# PowersupplyCommutation.net
KiCad netlist of a schematic drawn in EAGLE
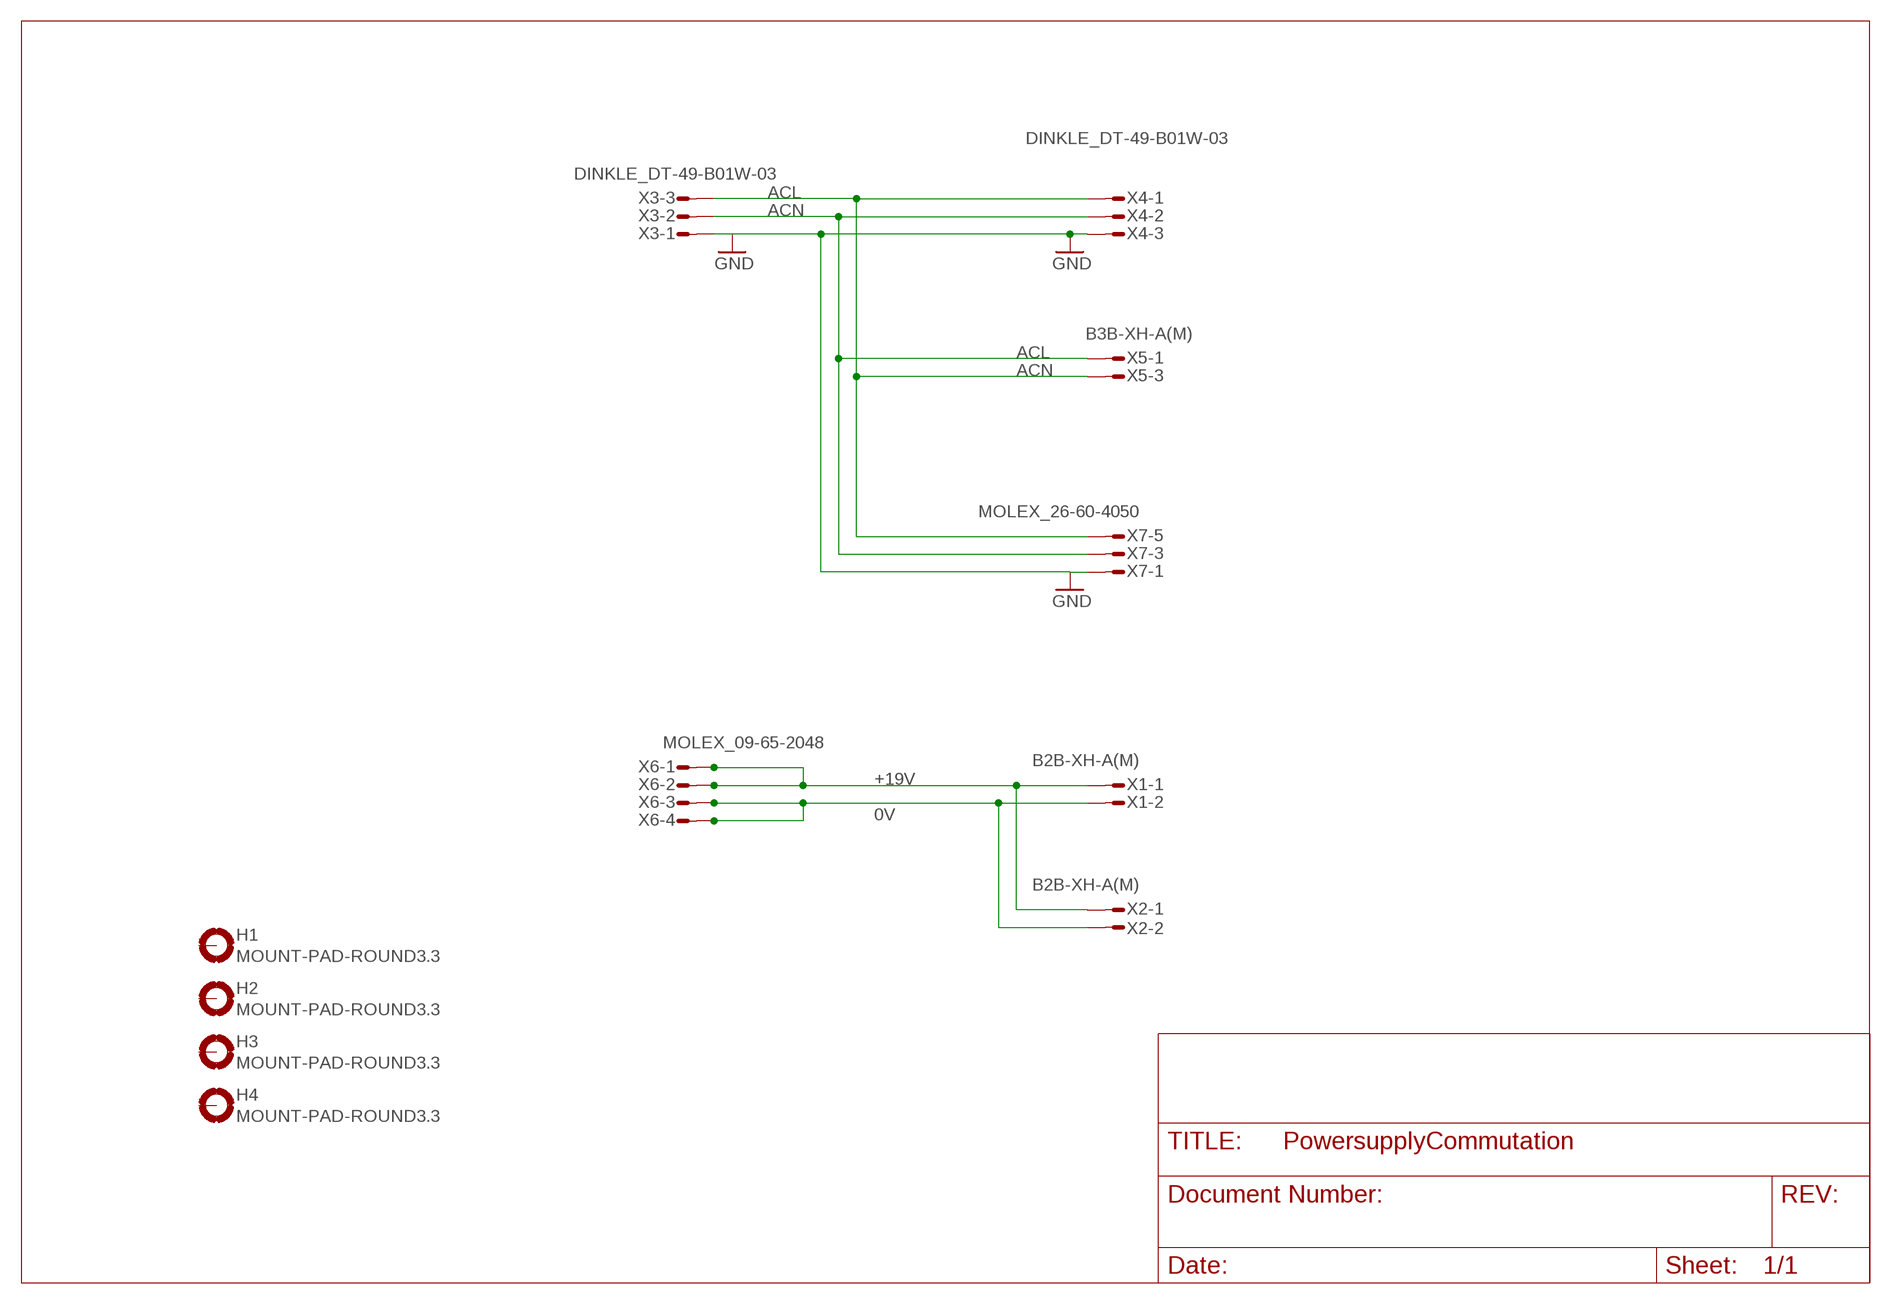
[diagram p0: schematic, sheet 1]

(export (version "E")
  (design (tool "Eeschema 10.0.6"))
  (components
    (comp (ref "H1")
      (value "MOUNT-PAD-ROUND3.3")
      (footprint "eagle-import:3,3-PAD")
      (libsource (lib "eagle-import") (part "MOUNT-PAD-ROUND3.3"))
    )
    (comp (ref "H2")
      (value "MOUNT-PAD-ROUND3.3")
      (footprint "eagle-import:3,3-PAD")
      (libsource (lib "eagle-import") (part "MOUNT-PAD-ROUND3.3"))
    )
    (comp (ref "H3")
      (value "MOUNT-PAD-ROUND3.3")
      (footprint "eagle-import:3,3-PAD")
      (libsource (lib "eagle-import") (part "MOUNT-PAD-ROUND3.3"))
    )
    (comp (ref "H4")
      (value "MOUNT-PAD-ROUND3.3")
      (footprint "eagle-import:3,3-PAD")
      (libsource (lib "eagle-import") (part "MOUNT-PAD-ROUND3.3"))
    )
    (comp (ref "X1")
      (value "B2B-XH-A(M)")
      (footprint "eagle-import:B2B-XH-AM")
      (libsource (lib "eagle-import") (part "B2B-XH-A(M)"))
    )
    (comp (ref "X2")
      (value "B2B-XH-A(M)")
      (footprint "eagle-import:B2B-XH-AM")
      (libsource (lib "eagle-import") (part "B2B-XH-A(M)"))
    )
    (comp (ref "X3")
      (value "DINKLE_DT-49-B01W-03")
      (footprint "eagle-import:DINKLE_DT-49-B01W-03")
      (libsource (lib "eagle-import") (part "DINKLE_DT-49-B01W-03"))
    )
    (comp (ref "X4")
      (value "DINKLE_DT-49-B01W-03")
      (footprint "eagle-import:DINKLE_DT-49-B01W-03")
      (libsource (lib "eagle-import") (part "DINKLE_DT-49-B01W-03"))
    )
    (comp (ref "X5")
      (value "B3B-XH-A(M)")
      (footprint "eagle-import:B3B-XH-AM")
      (libsource (lib "eagle-import") (part "B3B-XH-A(M)"))
    )
    (comp (ref "X6")
      (value "MOLEX_09-65-2048")
      (footprint "eagle-import:MOLEX_09-65-2048")
      (libsource (lib "eagle-import") (part "MOLEX_09-65-2048"))
    )
    (comp (ref "X7")
      (value "MOLEX_26-60-4050")
      (footprint "eagle-import:MOLEX_26-60-4050")
      (libsource (lib "eagle-import") (part "MOLEX_26-60-4050"))
    )
  )
  (nets
    (net (code "1") (name "/+19V") (class "Default")
      (node (ref "X1") (pin "1") (pinfunction "S_1") (pintype "passive"))
      (node (ref "X2") (pin "1") (pinfunction "S_1") (pintype "passive"))
      (node (ref "X6") (pin "1") (pinfunction "S_1") (pintype "passive"))
      (node (ref "X6") (pin "2") (pinfunction "S_2") (pintype "passive"))
    )
    (net (code "2") (name "/0V") (class "Default")
      (node (ref "X1") (pin "2") (pinfunction "S_2") (pintype "passive"))
      (node (ref "X2") (pin "2") (pinfunction "S_2") (pintype "passive"))
      (node (ref "X6") (pin "3") (pinfunction "S_3") (pintype "passive"))
      (node (ref "X6") (pin "4") (pinfunction "S_4") (pintype "passive"))
    )
    (net (code "3") (name "/ACL") (class "Default")
      (node (ref "X3") (pin "3") (pinfunction "S_3") (pintype "passive"))
      (node (ref "X4") (pin "1") (pinfunction "S_1") (pintype "passive"))
      (node (ref "X5") (pin "3") (pinfunction "S_3") (pintype "passive"))
      (node (ref "X7") (pin "5") (pinfunction "S_5") (pintype "passive"))
    )
    (net (code "4") (name "/ACN") (class "Default")
      (node (ref "X3") (pin "2") (pinfunction "S_2") (pintype "passive"))
      (node (ref "X4") (pin "2") (pinfunction "S_2") (pintype "passive"))
      (node (ref "X5") (pin "1") (pinfunction "S_1") (pintype "passive"))
      (node (ref "X7") (pin "3") (pinfunction "S_3") (pintype "passive"))
    )
    (net (code "5") (name "GND") (class "Default")
      (node (ref "X3") (pin "1") (pinfunction "S_1") (pintype "passive"))
      (node (ref "X4") (pin "3") (pinfunction "S_3") (pintype "passive"))
      (node (ref "X7") (pin "1") (pinfunction "S_1") (pintype "passive"))
    )
    (net (code "6") (name "unconnected-(H1-MOUNT-PadB3,3)") (class "Default")
      (node (ref "H1") (pin "B3,3") (pinfunction "MOUNT_B3,3") (pintype "passive"))
    )
    (net (code "7") (name "unconnected-(H2-MOUNT-PadB3,3)") (class "Default")
      (node (ref "H2") (pin "B3,3") (pinfunction "MOUNT_B3,3") (pintype "passive"))
    )
    (net (code "8") (name "unconnected-(H3-MOUNT-PadB3,3)") (class "Default")
      (node (ref "H3") (pin "B3,3") (pinfunction "MOUNT_B3,3") (pintype "passive"))
    )
    (net (code "9") (name "unconnected-(H4-MOUNT-PadB3,3)") (class "Default")
      (node (ref "H4") (pin "B3,3") (pinfunction "MOUNT_B3,3") (pintype "passive"))
    )
  )
)
